# Uni4lay-1_0.net
KiCad netlist of a schematic drawn in EAGLE
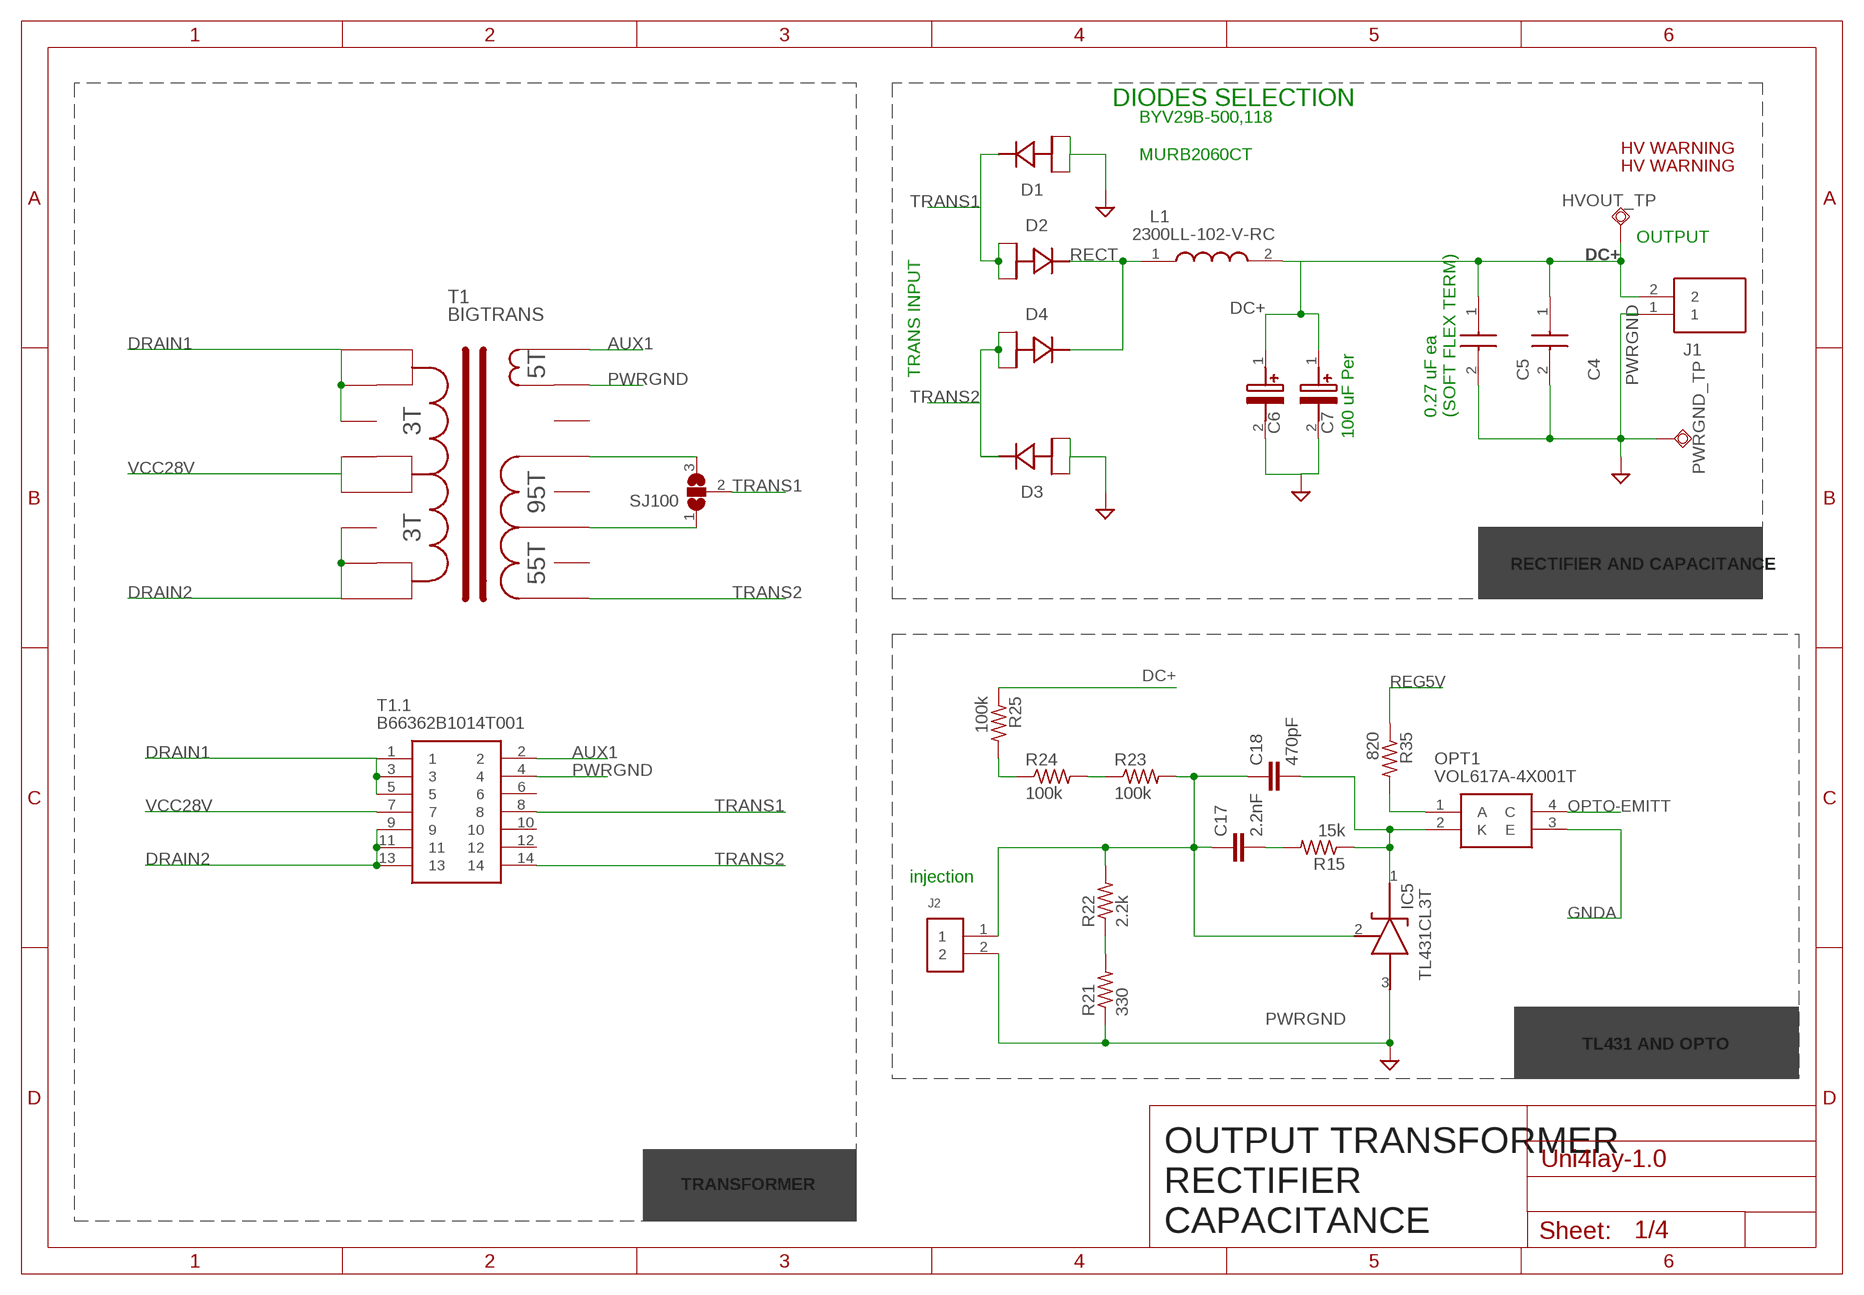
[diagram p0: schematic, sheet 1]
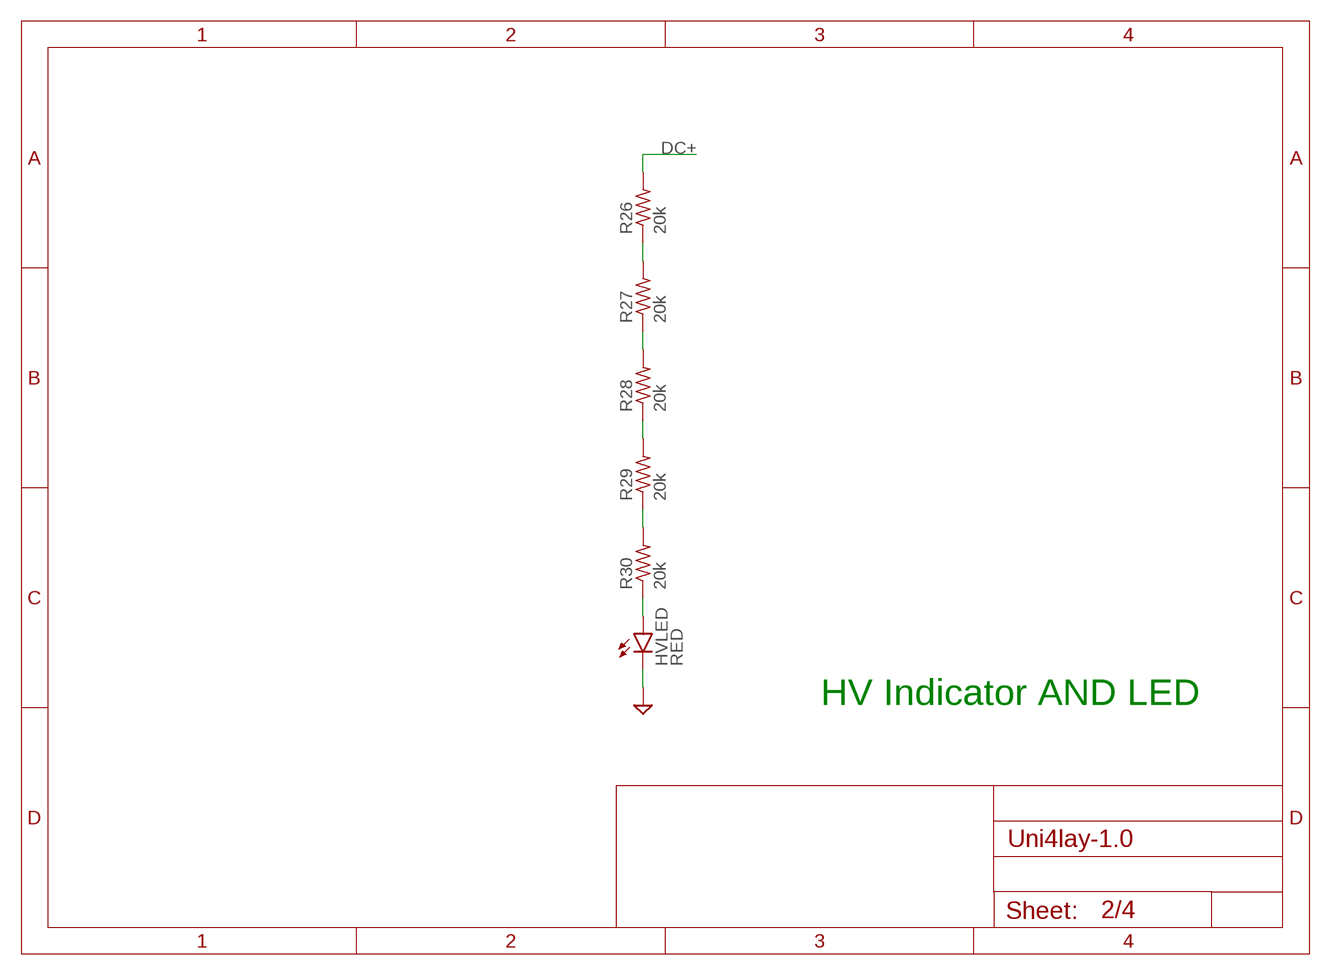
[diagram p1: schematic, sheet 2]
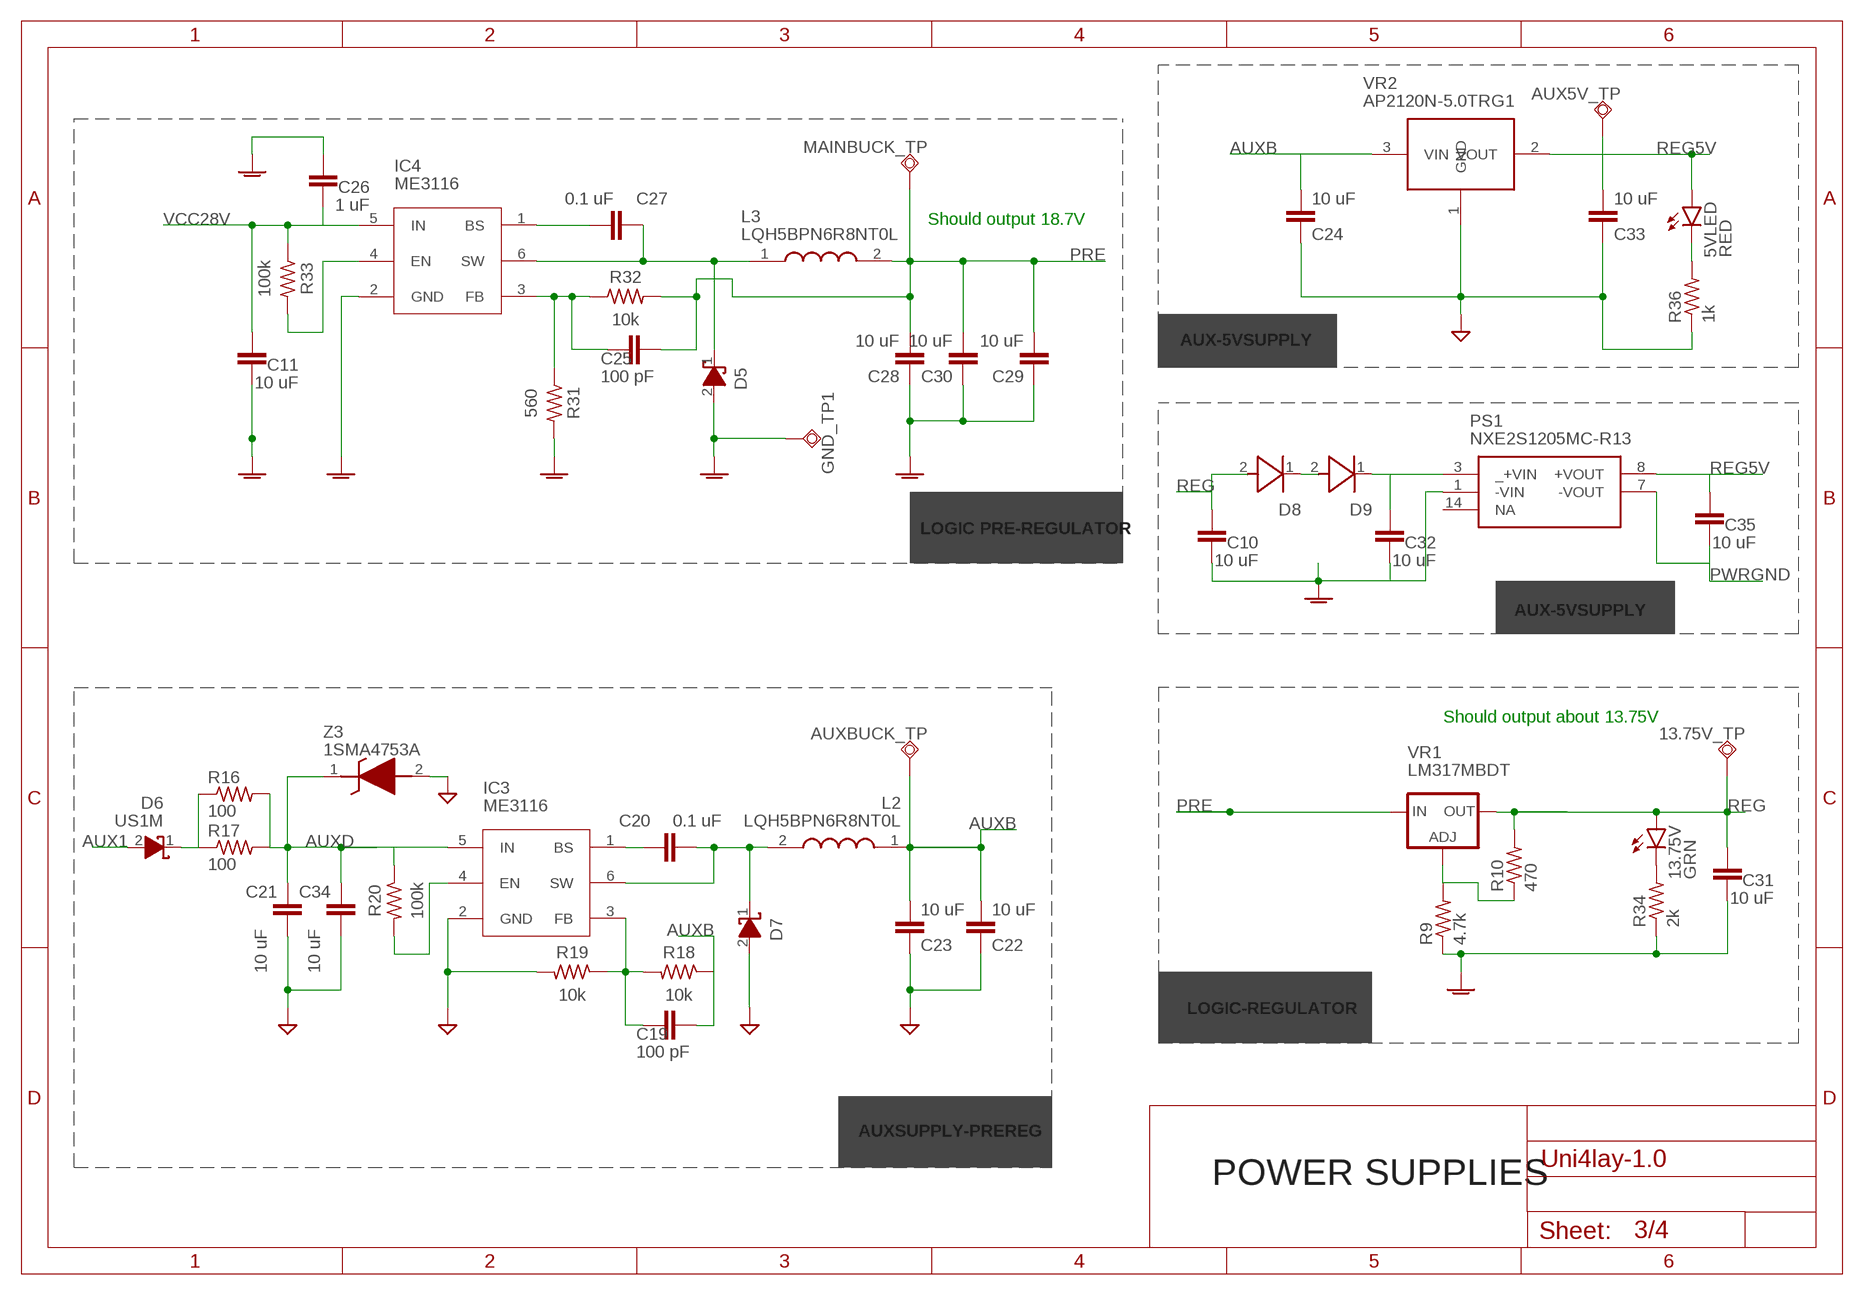
[diagram p2: schematic, sheet 3]
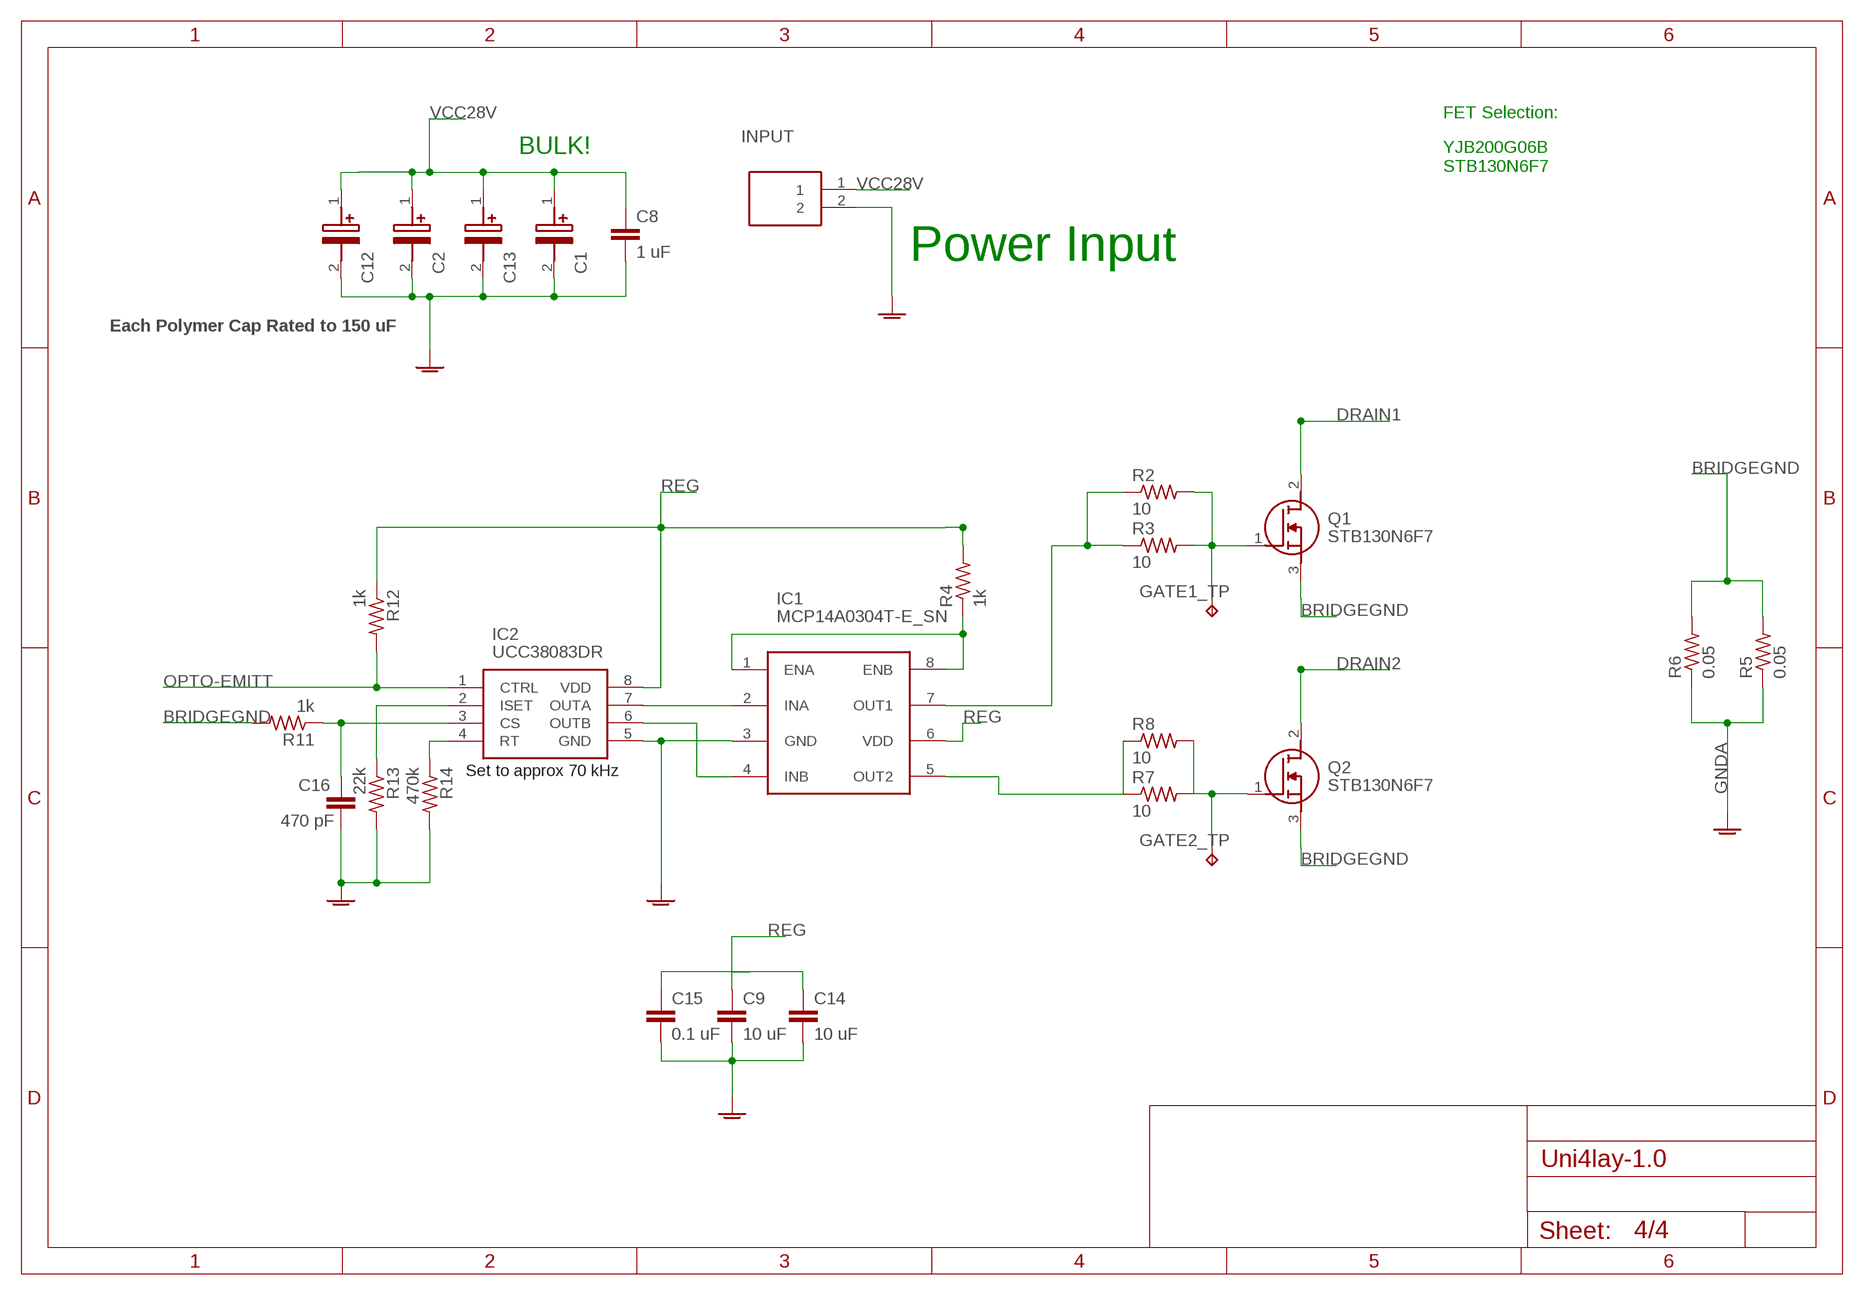
[diagram p3: schematic, sheet 4]

(export (version "E")
  (design (tool "Eeschema 10.0.6"))
  (components
    (comp (ref "C4")
      (value "C1812C274KCRACAUTO")
      (footprint "eagle-import:C1812")
      (fields (field (name "MOUSER_PART_NUMBER") "80-C1812C274KCRAUTO"))
      (libsource (lib "eagle-import") (part "C1812C274KCRACAUTO"))
    )
    (comp (ref "C5")
      (value "C1812C274KCRACAUTO")
      (footprint "eagle-import:C1812")
      (fields (field (name "MOUSER_PART_NUMBER") "80-C1812C274KCRAUTO"))
      (libsource (lib "eagle-import") (part "C1812C274KCRACAUTO"))
    )
    (comp (ref "C6")
      (value "400BXW100MEFR18X25")
      (footprint "eagle-import:CAPPRD750W80D1825H2700")
      (libsource (lib "eagle-import") (part "400BXW100MEFR18X25"))
    )
    (comp (ref "C7")
      (value "400BXW100MEFR18X25")
      (footprint "eagle-import:CAPPRD750W80D1825H2700")
      (libsource (lib "eagle-import") (part "400BXW100MEFR18X25"))
    )
    (comp (ref "C17")
      (value "2.2nF")
      (footprint "eagle-import:C0603K")
      (libsource (lib "eagle-import") (part "rcl_334_C-EUC0603K"))
    )
    (comp (ref "C18")
      (value "470pF")
      (footprint "eagle-import:C0603K")
      (libsource (lib "eagle-import") (part "rcl_334_C-EUC0603K"))
    )
    (comp (ref "D1")
      (value "FERD20H60CG-TR")
      (footprint "eagle-import:STB20N95K5")
      (fields (field (name "MOUSER_PART_NUMBER") "511-FERD20H60CG-TR"))
      (libsource (lib "eagle-import") (part "FERD20H60CG-TR"))
    )
    (comp (ref "D2")
      (value "FERD20H60CG-TR")
      (footprint "eagle-import:STB20N95K5")
      (fields (field (name "MOUSER_PART_NUMBER") "511-FERD20H60CG-TR"))
      (libsource (lib "eagle-import") (part "FERD20H60CG-TR"))
    )
    (comp (ref "D3")
      (value "FERD20H60CG-TR")
      (footprint "eagle-import:STB20N95K5")
      (fields (field (name "MOUSER_PART_NUMBER") "511-FERD20H60CG-TR"))
      (libsource (lib "eagle-import") (part "FERD20H60CG-TR"))
    )
    (comp (ref "D4")
      (value "FERD20H60CG-TR")
      (footprint "eagle-import:STB20N95K5")
      (fields (field (name "MOUSER_PART_NUMBER") "511-FERD20H60CG-TR"))
      (libsource (lib "eagle-import") (part "FERD20H60CG-TR"))
    )
    (comp (ref "HVOUT_TP")
      (value "TPSQPAD1-13")
      (footprint "eagle-import:P1-13")
      (libsource (lib "eagle-import") (part "TPSQPAD1-13"))
    )
    (comp (ref "IC5")
      (value "TL431CL3T")
      (footprint "eagle-import:SOT95P237X112-3N")
      (fields (field (name "MOUSER_PART_NUMBER") "511-TL431CL3T"))
      (libsource (lib "eagle-import") (part "TL431CL3T"))
    )
    (comp (ref "J1")
      (value "TB005-762-02BE")
      (footprint "eagle-import:TB00576202BE")
      (fields (field (name "MOUSER_PART_NUMBER") "490-TB005-762-02BE"))
      (libsource (lib "eagle-import") (part "TB005-762-02BE"))
    )
    (comp (ref "J2")
      (value "61300211121")
      (footprint "eagle-import:61300211121")
      (fields
        (field (name "DIGI_KEY_PART_NUMBER") "732-5315-ND")
        (field (name "MANUFACTURER") "Wurth Electronics Inc.")
        (field (name "CREATED_BY") "PCBLayout.com")
      )
      (libsource (lib "eagle-import") (part "61300211121"))
    )
    (comp (ref "L1")
      (value "2300LL-102-V-RC")
      (footprint "eagle-import:2300LL102VRC")
      (fields (field (name "MOUSER_PART_NUMBER") "652-2300LL-102-V-RC"))
      (libsource (lib "eagle-import") (part "2300LL-102-V-RC"))
    )
    (comp (ref "OPT1")
      (value "VOL617A-4X001T")
      (footprint "eagle-import:SOP254P1015X230-4N")
      (fields (field (name "MOUSER_PART_NUMBER") "78-VOL617A-4X001T"))
      (libsource (lib "eagle-import") (part "VOL617A-4X001T"))
    )
    (comp (ref "PWRGND_TP")
      (value "TPSQPAD1-13")
      (footprint "eagle-import:P1-13")
      (libsource (lib "eagle-import") (part "TPSQPAD1-13"))
    )
    (comp (ref "R15")
      (value "15k")
      (footprint "eagle-import:R0603")
      (libsource (lib "eagle-import") (part "R-US_R0603"))
    )
    (comp (ref "R21")
      (value "330")
      (footprint "eagle-import:R0805")
      (libsource (lib "eagle-import") (part "R-US_R0805"))
    )
    (comp (ref "R22")
      (value "2.2k")
      (footprint "eagle-import:R0805")
      (libsource (lib "eagle-import") (part "R-US_R0805"))
    )
    (comp (ref "R23")
      (value "100k")
      (footprint "eagle-import:R1206")
      (libsource (lib "eagle-import") (part "R-US_R1206"))
    )
    (comp (ref "R24")
      (value "100k")
      (footprint "eagle-import:R1206")
      (libsource (lib "eagle-import") (part "R-US_R1206"))
    )
    (comp (ref "R25")
      (value "100k")
      (footprint "eagle-import:R1206")
      (libsource (lib "eagle-import") (part "R-US_R1206"))
    )
    (comp (ref "R35")
      (value "820")
      (footprint "eagle-import:R0603")
      (libsource (lib "eagle-import") (part "R-US_R0603"))
    )
    (comp (ref "SJ100")
      (value "SJ2WW")
      (footprint "eagle-import:SJ_2W")
      (libsource (lib "eagle-import") (part "SJ2WW"))
    )
    (comp (ref "T1")
      (value "BIGTRANS")
      (footprint "eagle-import:BIGTRANS!")
      (libsource (lib "eagle-import") (part "BIGTRANS"))
    )
    (comp (ref "T1.1")
      (value "B66362B1014T001")
      (footprint "eagle-import:B66362B1014T001")
      (fields (field (name "MOUSER_PART_NUMBER") "871-B66362B1014T001"))
      (libsource (lib "eagle-import") (part "B66362B1014T001"))
    )
    (comp (ref "U$3")
      (value "HV")
      (footprint "eagle-import:PSFBC_ELECTRIC_SHOCK")
      (libsource (lib "eagle-import") (part "HV"))
    )
    (comp (ref "U$4")
      (value "HV")
      (footprint "eagle-import:PSFBC_ELECTRIC_SHOCK")
      (libsource (lib "eagle-import") (part "HV"))
    )
    (comp (ref "C1")
      (value "OVK151M1VTR-10131")
      (footprint "eagle-import:16SVF1000M")
      (libsource (lib "eagle-import") (part "OVK151M1VTR-10131"))
    )
    (comp (ref "C2")
      (value "OVK151M1VTR-10131")
      (footprint "eagle-import:16SVF1000M")
      (libsource (lib "eagle-import") (part "OVK151M1VTR-10131"))
    )
    (comp (ref "C8")
      (value "1 uF")
      (footprint "eagle-import:C0805K")
      (fields (field (name "LCSC_PART") "C440198"))
      (libsource (lib "eagle-import") (part "rcl_334_C-EUC0805K"))
    )
    (comp (ref "C9")
      (value "10 uF")
      (footprint "eagle-import:C0603K")
      (fields (field (name "LCSC_PART") "C440198"))
      (libsource (lib "eagle-import") (part "rcl_334_C-EUC0603K"))
    )
    (comp (ref "C12")
      (value "OVK151M1VTR-10131")
      (footprint "eagle-import:16SVF1000M")
      (libsource (lib "eagle-import") (part "OVK151M1VTR-10131"))
    )
    (comp (ref "C13")
      (value "OVK151M1VTR-10131")
      (footprint "eagle-import:16SVF1000M")
      (libsource (lib "eagle-import") (part "OVK151M1VTR-10131"))
    )
    (comp (ref "C14")
      (value "10 uF")
      (footprint "eagle-import:C0603K")
      (fields (field (name "LCSC_PART") "C440198"))
      (libsource (lib "eagle-import") (part "rcl_334_C-EUC0603K"))
    )
    (comp (ref "C15")
      (value "0.1 uF")
      (footprint "eagle-import:C0603K")
      (fields (field (name "LCSC_PART") "C440198"))
      (libsource (lib "eagle-import") (part "rcl_334_C-EUC0603K"))
    )
    (comp (ref "C16")
      (value "470 pF")
      (footprint "eagle-import:C0603K")
      (fields (field (name "LCSC_PART") "C1620"))
      (libsource (lib "eagle-import") (part "rcl_334_C-EUC0603K"))
    )
    (comp (ref "GATE1_TP")
      (value "TPTP13R")
      (footprint "eagle-import:TP13R")
      (libsource (lib "eagle-import") (part "TPTP13R"))
    )
    (comp (ref "GATE2_TP")
      (value "TPTP13R")
      (footprint "eagle-import:TP13R")
      (libsource (lib "eagle-import") (part "TPTP13R"))
    )
    (comp (ref "IC1")
      (value "MCP14A0304T-E_SN")
      (footprint "eagle-import:SOIC127P600X175-8N")
      (fields
        (field (name "MANUFACTURER_PART_NUMBER") "MCP14A0304T-E/SN")
        (field (name "MOUSER_PART_NUMBER") "579-MCP14A0304T-E/SN")
      )
      (libsource (lib "eagle-import") (part "MCP14A0304T-E_SN"))
    )
    (comp (ref "IC2")
      (value "UCC38083DR")
      (footprint "eagle-import:SOIC127P600X175-8N")
      (fields (field (name "MOUSER_PART_NUMBER") "595-UCC38083DR"))
      (libsource (lib "eagle-import") (part "UCC38083DR"))
    )
    (comp (ref "INPUT")
      (value "TB005-762-02BE")
      (footprint "eagle-import:TB00576202BE")
      (fields (field (name "MOUSER_PART_NUMBER") "490-TB005-762-02BE"))
      (libsource (lib "eagle-import") (part "TB005-762-02BE"))
    )
    (comp (ref "Q1")
      (value "STB130N6F7")
      (footprint "eagle-import:D2PAK")
      (libsource (lib "eagle-import") (part "STB130N6F7"))
    )
    (comp (ref "Q2")
      (value "STB130N6F7")
      (footprint "eagle-import:D2PAK")
      (libsource (lib "eagle-import") (part "STB130N6F7"))
    )
    (comp (ref "R2")
      (value "10")
      (footprint "eagle-import:R0805")
      (libsource (lib "eagle-import") (part "R-US_R0805"))
    )
    (comp (ref "R3")
      (value "10")
      (footprint "eagle-import:R0805")
      (libsource (lib "eagle-import") (part "R-US_R0805"))
    )
    (comp (ref "R4")
      (value "1k")
      (footprint "eagle-import:R0402")
      (libsource (lib "eagle-import") (part "R-US_R0402"))
    )
    (comp (ref "R5")
      (value "0.05")
      (footprint "eagle-import:R2512")
      (libsource (lib "eagle-import") (part "R-US_R2512"))
    )
    (comp (ref "R6")
      (value "0.05")
      (footprint "eagle-import:R2512")
      (libsource (lib "eagle-import") (part "R-US_R2512"))
    )
    (comp (ref "R7")
      (value "10")
      (footprint "eagle-import:R0805")
      (libsource (lib "eagle-import") (part "R-US_R0805"))
    )
    (comp (ref "R8")
      (value "10")
      (footprint "eagle-import:R0805")
      (libsource (lib "eagle-import") (part "R-US_R0805"))
    )
    (comp (ref "R11")
      (value "1k")
      (footprint "eagle-import:R0603")
      (fields (field (name "LCSC_PART") "C21190"))
      (libsource (lib "eagle-import") (part "R-US_R0603"))
    )
    (comp (ref "R12")
      (value "1k")
      (footprint "eagle-import:R0603")
      (fields (field (name "LCSC_PART") "C22975"))
      (libsource (lib "eagle-import") (part "R-US_R0603"))
    )
    (comp (ref "R13")
      (value "22k")
      (footprint "eagle-import:R0603")
      (fields (field (name "LCSC_PART") "C31850"))
      (libsource (lib "eagle-import") (part "R-US_R0603"))
    )
    (comp (ref "R14")
      (value "470k")
      (footprint "eagle-import:R0603")
      (fields (field (name "LCSC_PART") "C25811"))
      (libsource (lib "eagle-import") (part "R-US_R0603"))
    )
    (comp (ref "5VLED")
      (value "RED")
      (footprint "eagle-import:CHIPLED_0805")
      (fields (field (name "LCSC_PART") "C72043"))
      (libsource (lib "eagle-import") (part "LEDCHIPLED_0805"))
    )
    (comp (ref "13.75V")
      (value "GRN")
      (footprint "eagle-import:CHIPLED_0805")
      (fields (field (name "LCSC_PART") "C72043"))
      (libsource (lib "eagle-import") (part "LEDCHIPLED_0805"))
    )
    (comp (ref "13.75V_TP")
      (value "TPSQPAD1-17")
      (footprint "eagle-import:P1-17")
      (libsource (lib "eagle-import") (part "TPSQPAD1-17"))
    )
    (comp (ref "AUX5V_TP")
      (value "TPSQPAD1-17")
      (footprint "eagle-import:P1-17")
      (libsource (lib "eagle-import") (part "TPSQPAD1-17"))
    )
    (comp (ref "AUXBUCK_TP")
      (value "TPSQPAD1-17")
      (footprint "eagle-import:P1-17")
      (libsource (lib "eagle-import") (part "TPSQPAD1-17"))
    )
    (comp (ref "C10")
      (value "10 uF")
      (footprint "eagle-import:C0805K")
      (fields (field (name "LCSC_PART") "C440198"))
      (libsource (lib "eagle-import") (part "C-EUC0805K"))
    )
    (comp (ref "C11")
      (value "10 uF")
      (footprint "eagle-import:C0805K")
      (fields (field (name "LCSC_PART") "C440198"))
      (libsource (lib "eagle-import") (part "C-EUC0805K"))
    )
    (comp (ref "C19")
      (value "100 pF")
      (footprint "eagle-import:C0402K")
      (fields (field (name "LCSC_PART") "C1546"))
      (libsource (lib "eagle-import") (part "rcl_334_C-EUC0402K"))
    )
    (comp (ref "C20")
      (value "0.1 uF")
      (footprint "eagle-import:C0603K")
      (fields (field (name "LCSC_PART") "C14663"))
      (libsource (lib "eagle-import") (part "rcl_334_C-EUC0603K"))
    )
    (comp (ref "C21")
      (value "10 uF")
      (footprint "eagle-import:C0805K")
      (libsource (lib "eagle-import") (part "rcl_334_C-EUC0805K"))
    )
    (comp (ref "C22")
      (value "10 uF")
      (footprint "eagle-import:C0402")
      (fields (field (name "LCSC_PART") "C440198"))
      (libsource (lib "eagle-import") (part "rcl_334_C-EUC0402"))
    )
    (comp (ref "C23")
      (value "10 uF")
      (footprint "eagle-import:C0603K")
      (fields (field (name "LCSC_PART") "C440198"))
      (libsource (lib "eagle-import") (part "rcl_334_C-EUC0603K"))
    )
    (comp (ref "C24")
      (value "10 uF")
      (footprint "eagle-import:C0603K")
      (fields (field (name "LCSC_PART") "C440198"))
      (libsource (lib "eagle-import") (part "rcl_334_C-EUC0603K"))
    )
    (comp (ref "C25")
      (value "100 pF")
      (footprint "eagle-import:C0402K")
      (fields (field (name "LCSC_PART") "C1546"))
      (libsource (lib "eagle-import") (part "rcl_334_C-EUC0402K"))
    )
    (comp (ref "C26")
      (value "1 uF")
      (footprint "eagle-import:C0603K")
      (fields (field (name "LCSC_PART") "C440198"))
      (libsource (lib "eagle-import") (part "rcl_334_C-EUC0603K"))
    )
    (comp (ref "C27")
      (value "0.1 uF")
      (footprint "eagle-import:C0603K")
      (fields (field (name "LCSC_PART") "C14663"))
      (libsource (lib "eagle-import") (part "rcl_334_C-EUC0603K"))
    )
    (comp (ref "C28")
      (value "10 uF")
      (footprint "eagle-import:C0805K")
      (fields (field (name "LCSC_PART") "C440198"))
      (libsource (lib "eagle-import") (part "C-EUC0805K"))
    )
    (comp (ref "C29")
      (value "10 uF")
      (footprint "eagle-import:C0805K")
      (fields (field (name "LCSC_PART") "C440198"))
      (libsource (lib "eagle-import") (part "C-EUC0805K"))
    )
    (comp (ref "C30")
      (value "10 uF")
      (footprint "eagle-import:C0805K")
      (fields (field (name "LCSC_PART") "C440198"))
      (libsource (lib "eagle-import") (part "C-EUC0805K"))
    )
    (comp (ref "C31")
      (value "10 uF")
      (footprint "eagle-import:C0805K")
      (fields (field (name "LCSC_PART") "C440198"))
      (libsource (lib "eagle-import") (part "C-EUC0805K"))
    )
    (comp (ref "C32")
      (value "10 uF")
      (footprint "eagle-import:C0603K")
      (fields (field (name "LCSC_PART") "C440198"))
      (libsource (lib "eagle-import") (part "rcl_334_C-EUC0603K"))
    )
    (comp (ref "C33")
      (value "10 uF")
      (footprint "eagle-import:C0603K")
      (libsource (lib "eagle-import") (part "rcl_334_C-EUC0603K"))
    )
    (comp (ref "C34")
      (value "10 uF")
      (footprint "eagle-import:C0805K")
      (libsource (lib "eagle-import") (part "rcl_334_C-EUC0805K"))
    )
    (comp (ref "C35")
      (value "10 uF")
      (footprint "eagle-import:C0603K")
      (fields (field (name "LCSC_PART") "C440198"))
      (libsource (lib "eagle-import") (part "rcl_334_C-EUC0603K"))
    )
    (comp (ref "D5")
      (value "SCHOTTKY")
      (footprint "eagle-import:DIOM5127X229N")
      (fields
        (field (name "MANUFACTURER_PART_NUMBER") "SS16HE3_B/H")
        (field (name "MOUSER_PART_NUMBER") "78-SS16HE3_B/H")
        (field (name "LCSC_PART") "C22452")
      )
      (libsource (lib "eagle-import") (part "SCHOTTKY"))
    )
    (comp (ref "D6")
      (value "US1M")
      (footprint "eagle-import:DIOM5127X229N")
      (fields
        (field (name "MANUFACTURER_PART_NUMBER") "SS16HE3_B/H")
        (field (name "MOUSER_PART_NUMBER") "78-SS16HE3_B/H")
      )
      (libsource (lib "eagle-import") (part "SCHOTTKY"))
    )
    (comp (ref "D7")
      (value "SCHOTTKY")
      (footprint "eagle-import:DIOM5127X229N")
      (fields
        (field (name "MANUFACTURER_PART_NUMBER") "SS16HE3_B/H")
        (field (name "MOUSER_PART_NUMBER") "78-SS16HE3_B/H")
        (field (name "LCSC_PART") "C22452")
      )
      (libsource (lib "eagle-import") (part "SCHOTTKY"))
    )
    (comp (ref "D8")
      (value "SM4007PL")
      (footprint "eagle-import:SOD3716X145N")
      (fields
        (field (name "MANUFACTURER_PART_NUMBER") "1N4148W-7-F")
        (field (name "MOUSER_PART_NUMBER") "621-1N4148W-F")
        (field (name "LCSC_PART") "C64898")
      )
      (libsource (lib "eagle-import") (part "1N4148W-7-F"))
    )
    (comp (ref "D9")
      (value "SM4007PL")
      (footprint "eagle-import:SOD3716X145N")
      (fields
        (field (name "MANUFACTURER_PART_NUMBER") "1N4148W-7-F")
        (field (name "MOUSER_PART_NUMBER") "621-1N4148W-F")
        (field (name "LCSC_PART") "C64898")
      )
      (libsource (lib "eagle-import") (part "1N4148W-7-F"))
    )
    (comp (ref "GND_TP1")
      (value "TPSQPAD1-13")
      (footprint "eagle-import:P1-13")
      (libsource (lib "eagle-import") (part "TPSQPAD1-13"))
    )
    (comp (ref "IC3")
      (value "ME3116")
      (footprint "eagle-import:SOT95P280X100-6N")
      (fields (field (name "LCSC_PART") "C97643"))
      (libsource (lib "eagle-import") (part "ME3116"))
    )
    (comp (ref "IC4")
      (value "ME3116")
      (footprint "eagle-import:SOT95P280X100-6N")
      (fields (field (name "LCSC_PART") "C97643"))
      (libsource (lib "eagle-import") (part "ME3116"))
    )
    (comp (ref "L2")
      (value "LQH5BPN6R8NT0L")
      (footprint "eagle-import:LQH5BPB100MT0L")
      (fields (field (name "MOUSER_PART_NUMBER") "81-LQH5BPN6R8NT0L0L"))
      (libsource (lib "eagle-import") (part "LQH5BPN6R8NT0L"))
    )
    (comp (ref "L3")
      (value "LQH5BPN6R8NT0L")
      (footprint "eagle-import:LQH5BPB100MT0L")
      (fields (field (name "MOUSER_PART_NUMBER") "81-LQH5BPN6R8NT0L0L"))
      (libsource (lib "eagle-import") (part "LQH5BPN6R8NT0L"))
    )
    (comp (ref "MAINBUCK_TP")
      (value "TPSQPAD1-17")
      (footprint "eagle-import:P1-17")
      (libsource (lib "eagle-import") (part "TPSQPAD1-17"))
    )
    (comp (ref "PS1")
      (value "NXE2S1205MC-R13")
      (footprint "eagle-import:NXE2S1205MCR13")
      (fields (field (name "MOUSER_PART_NUMBER") "580-NXE2S1205MC-R13"))
      (libsource (lib "eagle-import") (part "NXE2S1205MC-R13"))
    )
    (comp (ref "R9")
      (value "4.7k")
      (footprint "eagle-import:R0603")
      (fields (field (name "LCSC_PART") "C22975"))
      (libsource (lib "eagle-import") (part "R-US_R0603"))
    )
    (comp (ref "R10")
      (value "470")
      (footprint "eagle-import:R0603")
      (fields (field (name "LCSC_PART") "C22975"))
      (libsource (lib "eagle-import") (part "R-US_R0603"))
    )
    (comp (ref "R16")
      (value "100")
      (footprint "eagle-import:R1206")
      (libsource (lib "eagle-import") (part "R-US_R1206"))
    )
    (comp (ref "R17")
      (value "100")
      (footprint "eagle-import:R1206")
      (libsource (lib "eagle-import") (part "R-US_R1206"))
    )
    (comp (ref "R18")
      (value "10k")
      (footprint "eagle-import:R0402")
      (fields (field (name "LCSC_PART") "C25779"))
      (libsource (lib "eagle-import") (part "R-US_R0402"))
    )
    (comp (ref "R19")
      (value "10k")
      (footprint "eagle-import:R0402")
      (fields (field (name "LCSC_PART") "C25779"))
      (libsource (lib "eagle-import") (part "R-US_R0402"))
    )
    (comp (ref "R20")
      (value "100k")
      (footprint "eagle-import:R0402")
      (fields (field (name "LCSC_PART") "C25741") (field (name "SPICEPREFIX") "R"))
      (libsource (lib "eagle-import") (part "R-US_R0402"))
    )
    (comp (ref "R31")
      (value "560")
      (footprint "eagle-import:R0402")
      (fields (field (name "LCSC_PART") "C4177") (field (name "SPICEPREFIX") "R"))
      (libsource (lib "eagle-import") (part "R-US_R0402"))
    )
    (comp (ref "R32")
      (value "10k")
      (footprint "eagle-import:R0402")
      (fields (field (name "LCSC_PART") "C25779"))
      (libsource (lib "eagle-import") (part "R-US_R0402"))
    )
    (comp (ref "R33")
      (value "100k")
      (footprint "eagle-import:R0402")
      (fields (field (name "LCSC_PART") "C25741") (field (name "SPICEPREFIX") "R"))
      (libsource (lib "eagle-import") (part "R-US_R0402"))
    )
    (comp (ref "R34")
      (value "2k")
      (footprint "eagle-import:R0603")
      (fields (field (name "LCSC_PART") "C22975"))
      (libsource (lib "eagle-import") (part "R-US_R0603"))
    )
    (comp (ref "R36")
      (value "1k")
      (footprint "eagle-import:R0603")
      (fields (field (name "LCSC_PART") "C22975"))
      (libsource (lib "eagle-import") (part "R-US_R0603"))
    )
    (comp (ref "VR1")
      (value "LM317MBDT")
      (footprint "eagle-import:DPACK")
      (libsource (lib "eagle-import") (part "LM317?MBDT"))
    )
    (comp (ref "VR2")
      (value "AP2120N-5.0TRG1")
      (footprint "eagle-import:SOT95P240X120-3N")
      (fields (field (name "MOUSER_PART_NUMBER") "621-AP2120N-5.0TRG1"))
      (libsource (lib "eagle-import") (part "AP2120N-5.0TRG1"))
    )
    (comp (ref "Z3")
      (value "1SMA4753A")
      (footprint "eagle-import:DIOM5226X220N")
      (fields
        (field (name "MANUFACTURER_PART_NUMBER") "1SMA5942BT3G")
        (field (name "MOUSER_PART_NUMBER") "863-1SMA5942BT3G")
        (field (name "LCSC_PART") "C362284")
      )
      (libsource (lib "eagle-import") (part "1SMA5942BT3G"))
    )
    (comp (ref "HVLED")
      (value "RED")
      (footprint "eagle-import:CHIPLED_0805")
      (libsource (lib "eagle-import") (part "LEDCHIPLED_0805"))
    )
    (comp (ref "R26")
      (value "20k")
      (footprint "eagle-import:R1206")
      (libsource (lib "eagle-import") (part "R-US_R1206"))
    )
    (comp (ref "R27")
      (value "20k")
      (footprint "eagle-import:R1206")
      (libsource (lib "eagle-import") (part "R-US_R1206"))
    )
    (comp (ref "R28")
      (value "20k")
      (footprint "eagle-import:R1206")
      (libsource (lib "eagle-import") (part "R-US_R1206"))
    )
    (comp (ref "R29")
      (value "20k")
      (footprint "eagle-import:R1206")
      (libsource (lib "eagle-import") (part "R-US_R1206"))
    )
    (comp (ref "R30")
      (value "20k")
      (footprint "eagle-import:R1206")
      (libsource (lib "eagle-import") (part "R-US_R1206"))
    )
  )
  (nets
    (net (code "1") (name "AUX1") (class "Default")
      (node (ref "D6") (pin "2") (pinfunction "A_2") (pintype "bidirectional"))
      (node (ref "T1") (pin "16") (pinfunction "16_16") (pintype "bidirectional"))
      (node (ref "T1.1") (pin "2") (pinfunction "2_2") (pintype "bidirectional"))
    )
    (net (code "2") (name "AUXB") (class "Default")
      (node (ref "AUXBUCK_TP") (pin "TP") (pinfunction "TP_TP") (pintype "input"))
      (node (ref "C19") (pin "1") (pinfunction "1_1") (pintype "passive"))
      (node (ref "C22") (pin "2") (pinfunction "2_2") (pintype "passive"))
      (node (ref "C23") (pin "2") (pinfunction "2_2") (pintype "passive"))
      (node (ref "C24") (pin "2") (pinfunction "2_2") (pintype "passive"))
      (node (ref "L2") (pin "1") (pinfunction "1_1") (pintype "bidirectional"))
      (node (ref "R18") (pin "1") (pinfunction "1_1") (pintype "passive"))
      (node (ref "VR2") (pin "3") (pinfunction "VIN_3") (pintype "bidirectional"))
    )
    (net (code "3") (name "AUXD") (class "Default")
      (node (ref "C21") (pin "1") (pinfunction "1_1") (pintype "passive"))
      (node (ref "C34") (pin "1") (pinfunction "1_1") (pintype "passive"))
      (node (ref "IC3") (pin "5") (pinfunction "IN_5") (pintype "bidirectional"))
      (node (ref "R16") (pin "2") (pinfunction "2_2") (pintype "passive"))
      (node (ref "R17") (pin "2") (pinfunction "2_2") (pintype "passive"))
      (node (ref "R20") (pin "1") (pinfunction "1_1") (pintype "passive"))
      (node (ref "Z3") (pin "1") (pinfunction "K_1") (pintype "bidirectional"))
    )
    (net (code "4") (name "BRIDGEGND") (class "Default")
      (node (ref "Q1") (pin "3") (pinfunction "S_3") (pintype "bidirectional"))
      (node (ref "Q2") (pin "3") (pinfunction "S_3") (pintype "bidirectional"))
      (node (ref "R11") (pin "2") (pinfunction "2_2") (pintype "passive"))
      (node (ref "R5") (pin "2") (pinfunction "2_2") (pintype "passive"))
      (node (ref "R6") (pin "2") (pinfunction "2_2") (pintype "passive"))
    )
    (net (code "5") (name "DC+") (class "Default")
      (node (ref "C4") (pin "1") (pinfunction "1_1") (pintype "bidirectional"))
      (node (ref "C5") (pin "1") (pinfunction "1_1") (pintype "bidirectional"))
      (node (ref "C6") (pin "1") (pinfunction "+_1") (pintype "bidirectional"))
      (node (ref "C7") (pin "1") (pinfunction "+_1") (pintype "bidirectional"))
      (node (ref "HVOUT_TP") (pin "TP") (pinfunction "TP_TP") (pintype "input"))
      (node (ref "J1") (pin "2") (pinfunction "2_2") (pintype "bidirectional"))
      (node (ref "L1") (pin "2") (pinfunction "2_2") (pintype "bidirectional"))
      (node (ref "R25") (pin "1") (pinfunction "1_1") (pintype "passive"))
      (node (ref "R26") (pin "2") (pinfunction "2_2") (pintype "passive"))
    )
    (net (code "6") (name "DRAIN1") (class "Default")
      (node (ref "Q1") (pin "2") (pinfunction "D_2") (pintype "bidirectional"))
      (node (ref "T1") (pin "6") (pinfunction "6_6") (pintype "bidirectional"))
      (node (ref "T1") (pin "7") (pinfunction "7_7") (pintype "bidirectional"))
      (node (ref "T1") (pin "8") (pinfunction "8_8") (pintype "bidirectional"))
      (node (ref "T1.1") (pin "1") (pinfunction "1_1") (pintype "bidirectional"))
      (node (ref "T1.1") (pin "3") (pinfunction "3_3") (pintype "bidirectional"))
      (node (ref "T1.1") (pin "5") (pinfunction "5_5") (pintype "bidirectional"))
    )
    (net (code "7") (name "DRAIN2") (class "Default")
      (node (ref "Q2") (pin "2") (pinfunction "D_2") (pintype "bidirectional"))
      (node (ref "T1") (pin "1") (pinfunction "1_1") (pintype "bidirectional"))
      (node (ref "T1") (pin "2") (pinfunction "2_2") (pintype "bidirectional"))
      (node (ref "T1") (pin "3") (pinfunction "3_3") (pintype "bidirectional"))
      (node (ref "T1.1") (pin "11") (pinfunction "11_11") (pintype "bidirectional"))
      (node (ref "T1.1") (pin "13") (pinfunction "13_13") (pintype "bidirectional"))
      (node (ref "T1.1") (pin "9") (pinfunction "9_9") (pintype "bidirectional"))
    )
    (net (code "8") (name "GNDA") (class "Default")
      (node (ref "C1") (pin "2") (pinfunction "-_2") (pintype "bidirectional"))
      (node (ref "C10") (pin "1") (pinfunction "1_1") (pintype "passive"))
      (node (ref "C11") (pin "1") (pinfunction "1_1") (pintype "passive"))
      (node (ref "C12") (pin "2") (pinfunction "-_2") (pintype "bidirectional"))
      (node (ref "C13") (pin "2") (pinfunction "-_2") (pintype "bidirectional"))
      (node (ref "C14") (pin "2") (pinfunction "2_2") (pintype "passive"))
      (node (ref "C15") (pin "2") (pinfunction "2_2") (pintype "passive"))
      (node (ref "C16") (pin "2") (pinfunction "2_2") (pintype "passive"))
      (node (ref "C2") (pin "2") (pinfunction "-_2") (pintype "bidirectional"))
      (node (ref "C26") (pin "2") (pinfunction "2_2") (pintype "passive"))
      (node (ref "C28") (pin "1") (pinfunction "1_1") (pintype "passive"))
      (node (ref "C29") (pin "1") (pinfunction "1_1") (pintype "passive"))
      (node (ref "C30") (pin "1") (pinfunction "1_1") (pintype "passive"))
      (node (ref "C31") (pin "1") (pinfunction "1_1") (pintype "passive"))
      (node (ref "C32") (pin "1") (pinfunction "1_1") (pintype "passive"))
      (node (ref "C8") (pin "2") (pinfunction "2_2") (pintype "passive"))
      (node (ref "C9") (pin "2") (pinfunction "2_2") (pintype "passive"))
      (node (ref "D5") (pin "2") (pinfunction "A_2") (pintype "bidirectional"))
      (node (ref "GND_TP1") (pin "TP") (pinfunction "TP_TP") (pintype "input"))
      (node (ref "IC1") (pin "3") (pinfunction "GND_3") (pintype "bidirectional"))
      (node (ref "IC2") (pin "5") (pinfunction "GND_5") (pintype "bidirectional"))
      (node (ref "IC4") (pin "2") (pinfunction "GND_2") (pintype "bidirectional"))
      (node (ref "INPUT") (pin "2") (pinfunction "2_2") (pintype "bidirectional"))
      (node (ref "OPT1") (pin "3") (pinfunction "E_3") (pintype "bidirectional"))
      (node (ref "PS1") (pin "1") (pinfunction "-VIN_1") (pintype "bidirectional"))
      (node (ref "R13") (pin "2") (pinfunction "2_2") (pintype "passive"))
      (node (ref "R14") (pin "2") (pinfunction "2_2") (pintype "passive"))
      (node (ref "R31") (pin "2") (pinfunction "2_2") (pintype "passive"))
      (node (ref "R34") (pin "1") (pinfunction "1_1") (pintype "passive"))
      (node (ref "R5") (pin "1") (pinfunction "1_1") (pintype "passive"))
      (node (ref "R6") (pin "1") (pinfunction "1_1") (pintype "passive"))
      (node (ref "R9") (pin "1") (pinfunction "1_1") (pintype "passive"))
    )
    (net (code "9") (name "Net-(5VLED-PadC)") (class "Default")
      (node (ref "5VLED") (pin "C") (pinfunction "C_C") (pintype "passive"))
      (node (ref "R36") (pin "2") (pinfunction "2_2") (pintype "passive"))
    )
    (net (code "10") (name "Net-(13.75V-PadC)") (class "Default")
      (node (ref "13.75V") (pin "C") (pinfunction "C_C") (pintype "passive"))
      (node (ref "R34") (pin "2") (pinfunction "2_2") (pintype "passive"))
    )
    (net (code "11") (name "Net-(C17-Pad2)") (class "Default")
      (node (ref "C17") (pin "2") (pinfunction "2_2") (pintype "passive"))
      (node (ref "R15") (pin "2") (pinfunction "2_2") (pintype "passive"))
    )
    (net (code "12") (name "Net-(D5-K)") (class "Default")
      (node (ref "C27") (pin "1") (pinfunction "1_1") (pintype "passive"))
      (node (ref "D5") (pin "1") (pinfunction "K_1") (pintype "bidirectional"))
      (node (ref "IC4") (pin "6") (pinfunction "SW_6") (pintype "bidirectional"))
      (node (ref "L3") (pin "1") (pinfunction "1_1") (pintype "bidirectional"))
    )
    (net (code "13") (name "Net-(D6-K)") (class "Default")
      (node (ref "D6") (pin "1") (pinfunction "K_1") (pintype "bidirectional"))
      (node (ref "R16") (pin "1") (pinfunction "1_1") (pintype "passive"))
      (node (ref "R17") (pin "1") (pinfunction "1_1") (pintype "passive"))
    )
    (net (code "14") (name "Net-(D7-K)") (class "Default")
      (node (ref "C20") (pin "2") (pinfunction "2_2") (pintype "passive"))
      (node (ref "D7") (pin "1") (pinfunction "K_1") (pintype "bidirectional"))
      (node (ref "IC3") (pin "6") (pinfunction "SW_6") (pintype "bidirectional"))
      (node (ref "L2") (pin "2") (pinfunction "2_2") (pintype "bidirectional"))
    )
    (net (code "15") (name "Net-(D8-K)") (class "Default")
      (node (ref "D8") (pin "1") (pinfunction "K_1") (pintype "bidirectional"))
      (node (ref "D9") (pin "2") (pinfunction "A_2") (pintype "bidirectional"))
    )
    (net (code "16") (name "Net-(D9-K)") (class "Default")
      (node (ref "C32") (pin "2") (pinfunction "2_2") (pintype "passive"))
      (node (ref "D9") (pin "1") (pinfunction "K_1") (pintype "bidirectional"))
      (node (ref "PS1") (pin "3") (pinfunction "_+VIN_3") (pintype "bidirectional"))
    )
    (net (code "17") (name "Net-(HVLED-PadA)") (class "Default")
      (node (ref "HVLED") (pin "A") (pinfunction "A_A") (pintype "passive"))
      (node (ref "R30") (pin "1") (pinfunction "1_1") (pintype "passive"))
    )
    (net (code "18") (name "Net-(IC1-ENA)") (class "Default")
      (node (ref "IC1") (pin "1") (pinfunction "ENA_1") (pintype "bidirectional"))
      (node (ref "IC1") (pin "8") (pinfunction "ENB_8") (pintype "bidirectional"))
      (node (ref "R4") (pin "1") (pinfunction "1_1") (pintype "passive"))
    )
    (net (code "19") (name "Net-(IC1-INA)") (class "Default")
      (node (ref "IC1") (pin "2") (pinfunction "INA_2") (pintype "bidirectional"))
      (node (ref "IC2") (pin "7") (pinfunction "OUTA_7") (pintype "bidirectional"))
    )
    (net (code "20") (name "Net-(IC1-INB)") (class "Default")
      (node (ref "IC1") (pin "4") (pinfunction "INB_4") (pintype "bidirectional"))
      (node (ref "IC2") (pin "6") (pinfunction "OUTB_6") (pintype "bidirectional"))
    )
    (net (code "21") (name "Net-(IC1-OUT1)") (class "Default")
      (node (ref "IC1") (pin "7") (pinfunction "OUT1_7") (pintype "bidirectional"))
      (node (ref "R2") (pin "1") (pinfunction "1_1") (pintype "passive"))
      (node (ref "R3") (pin "1") (pinfunction "1_1") (pintype "passive"))
    )
    (net (code "22") (name "Net-(IC1-OUT2)") (class "Default")
      (node (ref "IC1") (pin "5") (pinfunction "OUT2_5") (pintype "bidirectional"))
      (node (ref "R7") (pin "1") (pinfunction "1_1") (pintype "passive"))
      (node (ref "R8") (pin "1") (pinfunction "1_1") (pintype "passive"))
    )
    (net (code "23") (name "Net-(IC2-CS)") (class "Default")
      (node (ref "C16") (pin "1") (pinfunction "1_1") (pintype "passive"))
      (node (ref "IC2") (pin "3") (pinfunction "CS_3") (pintype "bidirectional"))
      (node (ref "R11") (pin "1") (pinfunction "1_1") (pintype "passive"))
    )
    (net (code "24") (name "Net-(IC2-ISET)") (class "Default")
      (node (ref "IC2") (pin "2") (pinfunction "ISET_2") (pintype "bidirectional"))
      (node (ref "R13") (pin "1") (pinfunction "1_1") (pintype "passive"))
    )
    (net (code "25") (name "Net-(IC2-RT)") (class "Default")
      (node (ref "IC2") (pin "4") (pinfunction "RT_4") (pintype "bidirectional"))
      (node (ref "R14") (pin "1") (pinfunction "1_1") (pintype "passive"))
    )
    (net (code "26") (name "Net-(IC3-BS)") (class "Default")
      (node (ref "C20") (pin "1") (pinfunction "1_1") (pintype "passive"))
      (node (ref "IC3") (pin "1") (pinfunction "BS_1") (pintype "bidirectional"))
    )
    (net (code "27") (name "Net-(IC3-EN)") (class "Default")
      (node (ref "IC3") (pin "4") (pinfunction "EN_4") (pintype "bidirectional"))
      (node (ref "R20") (pin "2") (pinfunction "2_2") (pintype "passive"))
    )
    (net (code "28") (name "Net-(IC3-FB)") (class "Default")
      (node (ref "C19") (pin "2") (pinfunction "2_2") (pintype "passive"))
      (node (ref "IC3") (pin "3") (pinfunction "FB_3") (pintype "bidirectional"))
      (node (ref "R18") (pin "2") (pinfunction "2_2") (pintype "passive"))
      (node (ref "R19") (pin "1") (pinfunction "1_1") (pintype "passive"))
    )
    (net (code "29") (name "Net-(IC4-BS)") (class "Default")
      (node (ref "C27") (pin "2") (pinfunction "2_2") (pintype "passive"))
      (node (ref "IC4") (pin "1") (pinfunction "BS_1") (pintype "bidirectional"))
    )
    (net (code "30") (name "Net-(IC4-EN)") (class "Default")
      (node (ref "IC4") (pin "4") (pinfunction "EN_4") (pintype "bidirectional"))
      (node (ref "R33") (pin "2") (pinfunction "2_2") (pintype "passive"))
    )
    (net (code "31") (name "Net-(IC4-FB)") (class "Default")
      (node (ref "C25") (pin "2") (pinfunction "2_2") (pintype "passive"))
      (node (ref "IC4") (pin "3") (pinfunction "FB_3") (pintype "bidirectional"))
      (node (ref "R31") (pin "1") (pinfunction "1_1") (pintype "passive"))
      (node (ref "R32") (pin "1") (pinfunction "1_1") (pintype "passive"))
    )
    (net (code "32") (name "Net-(IC5-CATHODE)") (class "Default")
      (node (ref "C18") (pin "2") (pinfunction "2_2") (pintype "passive"))
      (node (ref "IC5") (pin "1") (pinfunction "CATHODE_1") (pintype "bidirectional"))
      (node (ref "OPT1") (pin "2") (pinfunction "K_2") (pintype "bidirectional"))
      (node (ref "R15") (pin "1") (pinfunction "1_1") (pintype "passive"))
    )
    (net (code "33") (name "Net-(IC5-REF)") (class "Default")
      (node (ref "C17") (pin "1") (pinfunction "1_1") (pintype "passive"))
      (node (ref "C18") (pin "1") (pinfunction "1_1") (pintype "passive"))
      (node (ref "IC5") (pin "2") (pinfunction "REF_2") (pintype "bidirectional"))
      (node (ref "J2") (pin "1") (pinfunction "1_1") (pintype "passive"))
      (node (ref "R22") (pin "2") (pinfunction "2_2") (pintype "passive"))
      (node (ref "R23") (pin "2") (pinfunction "2_2") (pintype "passive"))
    )
    (net (code "34") (name "Net-(OPT1-A)") (class "Default")
      (node (ref "OPT1") (pin "1") (pinfunction "A_1") (pintype "bidirectional"))
      (node (ref "R35") (pin "2") (pinfunction "2_2") (pintype "passive"))
    )
    (net (code "35") (name "Net-(Q1-G)") (class "Default")
      (node (ref "GATE1_TP") (pin "TP") (pinfunction "TP_TP") (pintype "input"))
      (node (ref "Q1") (pin "1") (pinfunction "G_1") (pintype "bidirectional"))
      (node (ref "R2") (pin "2") (pinfunction "2_2") (pintype "passive"))
      (node (ref "R3") (pin "2") (pinfunction "2_2") (pintype "passive"))
    )
    (net (code "36") (name "Net-(Q2-G)") (class "Default")
      (node (ref "GATE2_TP") (pin "TP") (pinfunction "TP_TP") (pintype "input"))
      (node (ref "Q2") (pin "1") (pinfunction "G_1") (pintype "bidirectional"))
      (node (ref "R7") (pin "2") (pinfunction "2_2") (pintype "passive"))
      (node (ref "R8") (pin "2") (pinfunction "2_2") (pintype "passive"))
    )
    (net (code "37") (name "Net-(R21-Pad2)") (class "Default")
      (node (ref "R21") (pin "2") (pinfunction "2_2") (pintype "passive"))
      (node (ref "R22") (pin "1") (pinfunction "1_1") (pintype "passive"))
    )
    (net (code "38") (name "Net-(R23-Pad1)") (class "Default")
      (node (ref "R23") (pin "1") (pinfunction "1_1") (pintype "passive"))
      (node (ref "R24") (pin "2") (pinfunction "2_2") (pintype "passive"))
    )
    (net (code "39") (name "Net-(R24-Pad1)") (class "Default")
      (node (ref "R24") (pin "1") (pinfunction "1_1") (pintype "passive"))
      (node (ref "R25") (pin "2") (pinfunction "2_2") (pintype "passive"))
    )
    (net (code "40") (name "Net-(R26-Pad1)") (class "Default")
      (node (ref "R26") (pin "1") (pinfunction "1_1") (pintype "passive"))
      (node (ref "R27") (pin "2") (pinfunction "2_2") (pintype "passive"))
    )
    (net (code "41") (name "Net-(R27-Pad1)") (class "Default")
      (node (ref "R27") (pin "1") (pinfunction "1_1") (pintype "passive"))
      (node (ref "R28") (pin "2") (pinfunction "2_2") (pintype "passive"))
    )
    (net (code "42") (name "Net-(R28-Pad1)") (class "Default")
      (node (ref "R28") (pin "1") (pinfunction "1_1") (pintype "passive"))
      (node (ref "R29") (pin "2") (pinfunction "2_2") (pintype "passive"))
    )
    (net (code "43") (name "Net-(R29-Pad1)") (class "Default")
      (node (ref "R29") (pin "1") (pinfunction "1_1") (pintype "passive"))
      (node (ref "R30") (pin "2") (pinfunction "2_2") (pintype "passive"))
    )
    (net (code "44") (name "Net-(SJ100-Pad1)") (class "Default")
      (node (ref "SJ100") (pin "1") (pinfunction "1_1") (pintype "passive"))
      (node (ref "T1") (pin "11") (pinfunction "11_11") (pintype "bidirectional"))
    )
    (net (code "45") (name "Net-(SJ100-Pad3)") (class "Default")
      (node (ref "SJ100") (pin "3") (pinfunction "3_3") (pintype "passive"))
      (node (ref "T1") (pin "13") (pinfunction "13_13") (pintype "bidirectional"))
    )
    (net (code "46") (name "Net-(VR1-ADJ)") (class "Default")
      (node (ref "R10") (pin "1") (pinfunction "1_1") (pintype "passive"))
      (node (ref "R9") (pin "2") (pinfunction "2_2") (pintype "passive"))
      (node (ref "VR1") (pin "1") (pinfunction "ADJ_1") (pintype "input"))
    )
    (net (code "47") (name "OPTO-EMITT") (class "Default")
      (node (ref "IC2") (pin "1") (pinfunction "CTRL_1") (pintype "bidirectional"))
      (node (ref "OPT1") (pin "4") (pinfunction "C_4") (pintype "bidirectional"))
      (node (ref "R12") (pin "2") (pinfunction "2_2") (pintype "passive"))
    )
    (net (code "48") (name "PRE") (class "Default")
      (node (ref "C25") (pin "1") (pinfunction "1_1") (pintype "passive"))
      (node (ref "C28") (pin "2") (pinfunction "2_2") (pintype "passive"))
      (node (ref "C29") (pin "2") (pinfunction "2_2") (pintype "passive"))
      (node (ref "C30") (pin "2") (pinfunction "2_2") (pintype "passive"))
      (node (ref "L3") (pin "2") (pinfunction "2_2") (pintype "bidirectional"))
      (node (ref "MAINBUCK_TP") (pin "TP") (pinfunction "TP_TP") (pintype "input"))
      (node (ref "R32") (pin "2") (pinfunction "2_2") (pintype "passive"))
      (node (ref "VR1") (pin "3") (pinfunction "IN_3") (pintype "input"))
    )
    (net (code "49") (name "PWRGND") (class "Default")
      (node (ref "C21") (pin "2") (pinfunction "2_2") (pintype "passive"))
      (node (ref "C22") (pin "1") (pinfunction "1_1") (pintype "passive"))
      (node (ref "C23") (pin "1") (pinfunction "1_1") (pintype "passive"))
      (node (ref "C24") (pin "1") (pinfunction "1_1") (pintype "passive"))
      (node (ref "C33") (pin "1") (pinfunction "1_1") (pintype "passive"))
      (node (ref "C34") (pin "2") (pinfunction "2_2") (pintype "passive"))
      (node (ref "C35") (pin "1") (pinfunction "1_1") (pintype "passive"))
      (node (ref "C4") (pin "2") (pinfunction "2_2") (pintype "bidirectional"))
      (node (ref "C5") (pin "2") (pinfunction "2_2") (pintype "bidirectional"))
      (node (ref "C6") (pin "2") (pinfunction "-_2") (pintype "bidirectional"))
      (node (ref "C7") (pin "2") (pinfunction "-_2") (pintype "bidirectional"))
      (node (ref "D1") (pin "1") (pinfunction "A1_1") (pintype "bidirectional"))
      (node (ref "D1") (pin "3") (pinfunction "A2_3") (pintype "bidirectional"))
      (node (ref "D3") (pin "1") (pinfunction "A1_1") (pintype "bidirectional"))
      (node (ref "D3") (pin "3") (pinfunction "A2_3") (pintype "bidirectional"))
      (node (ref "D7") (pin "2") (pinfunction "A_2") (pintype "bidirectional"))
      (node (ref "HVLED") (pin "C") (pinfunction "C_C") (pintype "passive"))
      (node (ref "IC3") (pin "2") (pinfunction "GND_2") (pintype "bidirectional"))
      (node (ref "IC5") (pin "3") (pinfunction "ANODE_3") (pintype "bidirectional"))
      (node (ref "J1") (pin "1") (pinfunction "1_1") (pintype "bidirectional"))
      (node (ref "J2") (pin "2") (pinfunction "2_2") (pintype "passive"))
      (node (ref "PS1") (pin "7") (pinfunction "-VOUT_7") (pintype "bidirectional"))
      (node (ref "PWRGND_TP") (pin "TP") (pinfunction "TP_TP") (pintype "input"))
      (node (ref "R19") (pin "2") (pinfunction "2_2") (pintype "passive"))
      (node (ref "R21") (pin "1") (pinfunction "1_1") (pintype "passive"))
      (node (ref "R36") (pin "1") (pinfunction "1_1") (pintype "passive"))
      (node (ref "T1") (pin "15") (pinfunction "15_15") (pintype "bidirectional"))
      (node (ref "T1.1") (pin "4") (pinfunction "4_4") (pintype "bidirectional"))
      (node (ref "VR2") (pin "1") (pinfunction "GND_1") (pintype "bidirectional"))
      (node (ref "Z3") (pin "2") (pinfunction "A_2") (pintype "bidirectional"))
    )
    (net (code "50") (name "RECT") (class "Default")
      (node (ref "D2") (pin "2") (pinfunction "K_2") (pintype "bidirectional"))
      (node (ref "D4") (pin "2") (pinfunction "K_2") (pintype "bidirectional"))
      (node (ref "L1") (pin "1") (pinfunction "1_1") (pintype "bidirectional"))
    )
    (net (code "51") (name "REG") (class "Default")
      (node (ref "13.75V") (pin "A") (pinfunction "A_A") (pintype "passive"))
      (node (ref "13.75V_TP") (pin "TP") (pinfunction "TP_TP") (pintype "input"))
      (node (ref "C10") (pin "2") (pinfunction "2_2") (pintype "passive"))
      (node (ref "C14") (pin "1") (pinfunction "1_1") (pintype "passive"))
      (node (ref "C15") (pin "1") (pinfunction "1_1") (pintype "passive"))
      (node (ref "C31") (pin "2") (pinfunction "2_2") (pintype "passive"))
      (node (ref "C9") (pin "1") (pinfunction "1_1") (pintype "passive"))
      (node (ref "D8") (pin "2") (pinfunction "A_2") (pintype "bidirectional"))
      (node (ref "IC1") (pin "6") (pinfunction "VDD_6") (pintype "bidirectional"))
      (node (ref "IC2") (pin "8") (pinfunction "VDD_8") (pintype "bidirectional"))
      (node (ref "R10") (pin "2") (pinfunction "2_2") (pintype "passive"))
      (node (ref "R12") (pin "1") (pinfunction "1_1") (pintype "passive"))
      (node (ref "R4") (pin "2") (pinfunction "2_2") (pintype "passive"))
      (node (ref "VR1") (pin "4") (pinfunction "OUT_4") (pintype "passive"))
    )
    (net (code "52") (name "REG5V") (class "Default")
      (node (ref "5VLED") (pin "A") (pinfunction "A_A") (pintype "passive"))
      (node (ref "AUX5V_TP") (pin "TP") (pinfunction "TP_TP") (pintype "input"))
      (node (ref "C33") (pin "2") (pinfunction "2_2") (pintype "passive"))
      (node (ref "C35") (pin "2") (pinfunction "2_2") (pintype "passive"))
      (node (ref "PS1") (pin "8") (pinfunction "+VOUT_8") (pintype "bidirectional"))
      (node (ref "R35") (pin "1") (pinfunction "1_1") (pintype "passive"))
      (node (ref "VR2") (pin "2") (pinfunction "VOUT_2") (pintype "bidirectional"))
    )
    (net (code "53") (name "TRANS1") (class "Default")
      (node (ref "D1") (pin "2") (pinfunction "K_2") (pintype "bidirectional"))
      (node (ref "D2") (pin "1") (pinfunction "A1_1") (pintype "bidirectional"))
      (node (ref "D2") (pin "3") (pinfunction "A2_3") (pintype "bidirectional"))
      (node (ref "SJ100") (pin "2") (pinfunction "2_2") (pintype "passive"))
      (node (ref "T1.1") (pin "8") (pinfunction "8_8") (pintype "bidirectional"))
    )
    (net (code "54") (name "TRANS2") (class "Default")
      (node (ref "D3") (pin "2") (pinfunction "K_2") (pintype "bidirectional"))
      (node (ref "D4") (pin "1") (pinfunction "A1_1") (pintype "bidirectional"))
      (node (ref "D4") (pin "3") (pinfunction "A2_3") (pintype "bidirectional"))
      (node (ref "T1") (pin "9") (pinfunction "9_9") (pintype "bidirectional"))
      (node (ref "T1.1") (pin "14") (pinfunction "14_14") (pintype "bidirectional"))
    )
    (net (code "55") (name "VCC28V") (class "Default")
      (node (ref "C1") (pin "1") (pinfunction "+_1") (pintype "bidirectional"))
      (node (ref "C11") (pin "2") (pinfunction "2_2") (pintype "passive"))
      (node (ref "C12") (pin "1") (pinfunction "+_1") (pintype "bidirectional"))
      (node (ref "C13") (pin "1") (pinfunction "+_1") (pintype "bidirectional"))
      (node (ref "C2") (pin "1") (pinfunction "+_1") (pintype "bidirectional"))
      (node (ref "C26") (pin "1") (pinfunction "1_1") (pintype "passive"))
      (node (ref "C8") (pin "1") (pinfunction "1_1") (pintype "passive"))
      (node (ref "IC4") (pin "5") (pinfunction "IN_5") (pintype "bidirectional"))
      (node (ref "INPUT") (pin "1") (pinfunction "1_1") (pintype "bidirectional"))
      (node (ref "R33") (pin "1") (pinfunction "1_1") (pintype "passive"))
      (node (ref "T1") (pin "4") (pinfunction "4_4") (pintype "bidirectional"))
      (node (ref "T1") (pin "5") (pinfunction "5_5") (pintype "bidirectional"))
      (node (ref "T1.1") (pin "7") (pinfunction "7_7") (pintype "bidirectional"))
    )
    (net (code "56") (name "unconnected-(PS1-NA-Pad14)") (class "Default")
      (node (ref "PS1") (pin "14") (pinfunction "NA_14") (pintype "bidirectional"))
    )
    (net (code "57") (name "unconnected-(T1-Pad10)") (class "Default")
      (node (ref "T1") (pin "10") (pinfunction "10_10") (pintype "bidirectional"))
    )
    (net (code "58") (name "unconnected-(T1-Pad12)") (class "Default")
      (node (ref "T1") (pin "12") (pinfunction "12_12") (pintype "bidirectional"))
    )
    (net (code "59") (name "unconnected-(T1-Pad14)") (class "Default")
      (node (ref "T1") (pin "14") (pinfunction "14_14") (pintype "bidirectional"))
    )
    (net (code "60") (name "unconnected-(T1.1-Pad6)") (class "Default")
      (node (ref "T1.1") (pin "6") (pinfunction "6_6") (pintype "bidirectional"))
    )
    (net (code "61") (name "unconnected-(T1.1-Pad10)") (class "Default")
      (node (ref "T1.1") (pin "10") (pinfunction "10_10") (pintype "bidirectional"))
    )
    (net (code "62") (name "unconnected-(T1.1-Pad12)") (class "Default")
      (node (ref "T1.1") (pin "12") (pinfunction "12_12") (pintype "bidirectional"))
    )
  )
)
